# ADC.net
KiCad netlist of a schematic drawn in Altium Designer
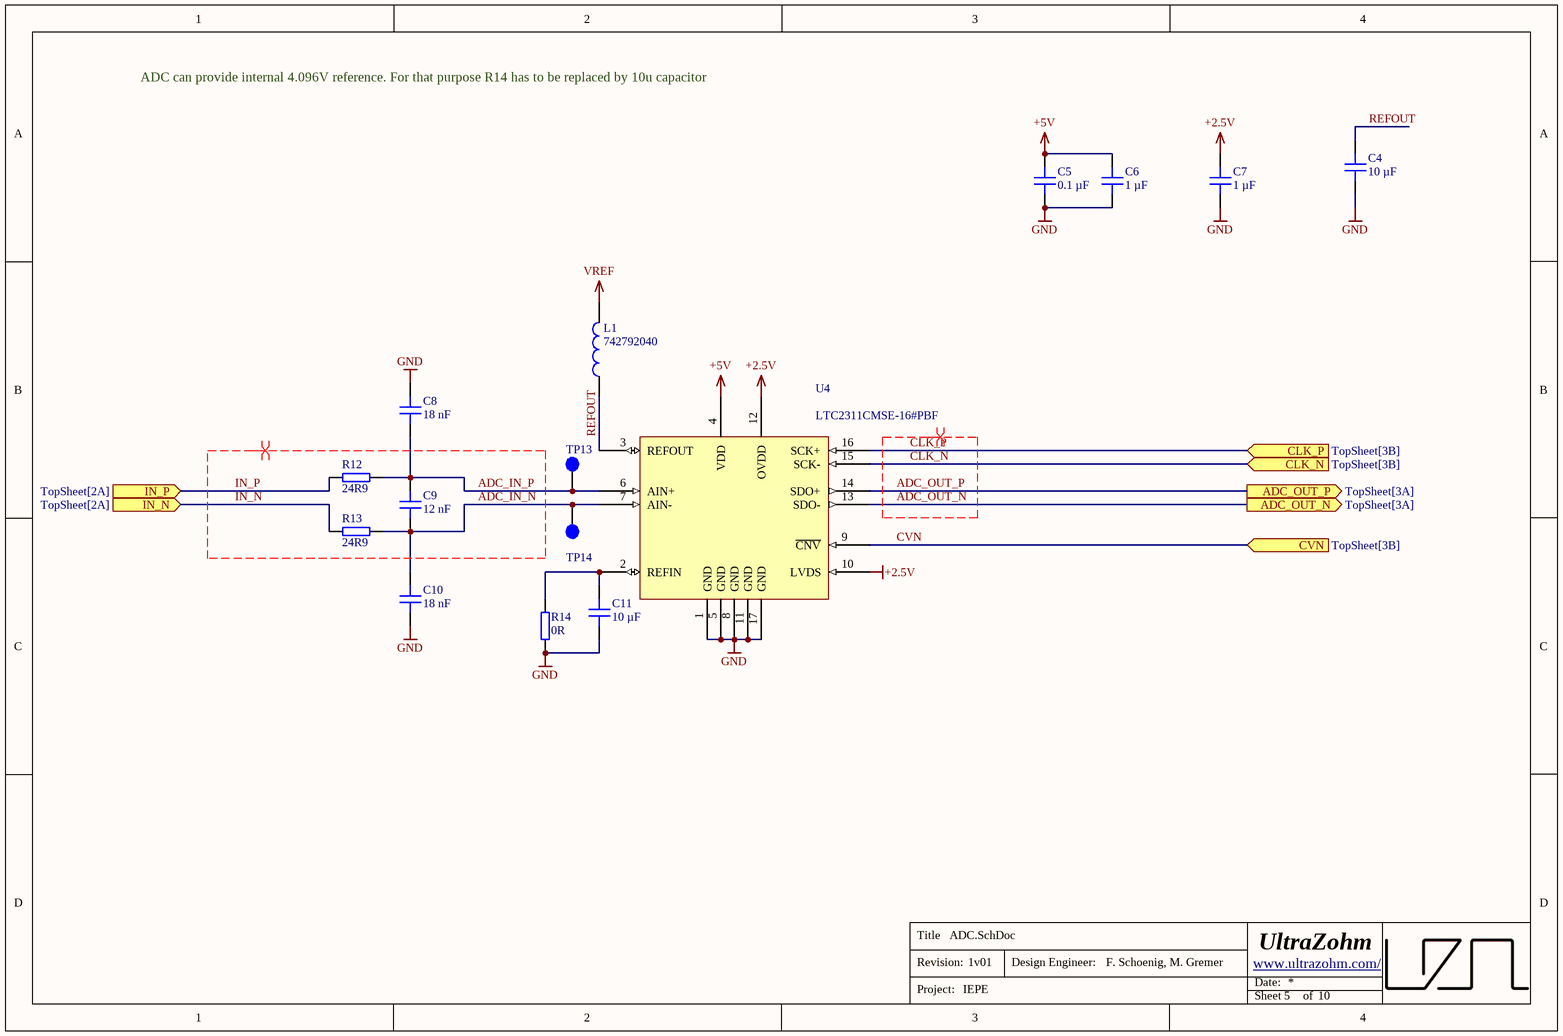
[diagram p0: ADC.SchDoc]

(export (version "E")
  (design (tool "Eeschema 10.0.6"))
  (components
    (comp (ref "C4")
      (value "10 µF")
      (footprint "C_0805")
      (description "Capacitor 0805, 25 VDC, 10 µF, X5R")
      (fields
        (field (name "MANUFACTURER PART NUMBER") "GRM219R61E106KA12D")
        (field (name "MANUFACTURER") "muRata")
        (field (name "CREATED FROM") "MGremer")
      )
      (libsource (lib "user") (part "Capacitor"))
    )
    (comp (ref "C5")
      (value "0.1 µF")
      (footprint "C_0603")
      (description "Capacitor 0603, 50 VDC, 0.1 µF, X7R")
      (fields
        (field (name "MANUFACTURER PART NUMBER") "C0603X104K5RAC7411")
        (field (name "MANUFACTURER") "KEMET")
        (field (name "CREATED FROM") "MGremer")
      )
      (libsource (lib "user") (part "Capacitor"))
    )
    (comp (ref "C6")
      (value "1 µF")
      (footprint "C_0603")
      (description "Capacitor 0603, 6.3 VDC, 1 µF, X7R")
      (fields
        (field (name "MANUFACTURER PART NUMBER") "JMK107BJ105MA-T")
        (field (name "MANUFACTURER") "Tajyo Yuden")
        (field (name "CREATED FROM") "MGremer")
      )
      (libsource (lib "user") (part "Capacitor"))
    )
    (comp (ref "C7")
      (value "1 µF")
      (footprint "C_0603")
      (description "Capacitor 0603, 6.3 VDC, 1 µF, X7R")
      (fields
        (field (name "MANUFACTURER PART NUMBER") "JMK107BJ105MA-T")
        (field (name "MANUFACTURER") "Tajyo Yuden")
        (field (name "CREATED FROM") "MGremer")
      )
      (libsource (lib "user") (part "Capacitor"))
    )
    (comp (ref "C8")
      (value "18 nF")
      (footprint "C_0603")
      (description "Capacitor 0603, 16 VDC, 18 nF, X7R")
      (fields
        (field (name "MANUFACTURER PART NUMBER") "C0603C183K4RACTU")
        (field (name "MANUFACTURER") "KEMET")
        (field (name "CREATED FROM") "MGremer")
      )
      (libsource (lib "user") (part "Capacitor"))
    )
    (comp (ref "C9")
      (value "12 nF")
      (footprint "C_0603")
      (description "Capacitor 0603, 16 VDC, 12 nF, X7R")
      (fields
        (field (name "MANUFACTURER PART NUMBER") "CC0603KRX7R7BB123")
        (field (name "MANUFACTURER") "Yageo")
        (field (name "CREATED FROM") "MGremer")
      )
      (libsource (lib "user") (part "Capacitor"))
    )
    (comp (ref "C10")
      (value "18 nF")
      (footprint "C_0603")
      (description "Capacitor 0603, 16 VDC, 18 nF, X7R")
      (fields
        (field (name "MANUFACTURER PART NUMBER") "C0603C183K4RACTU")
        (field (name "MANUFACTURER") "KEMET")
        (field (name "CREATED FROM") "MGremer")
      )
      (libsource (lib "user") (part "Capacitor"))
    )
    (comp (ref "C11")
      (value "10 µF")
      (footprint "C_0805")
      (description "Capacitor 0805, 25 VDC, 10 µF, X5R")
      (fields
        (field (name "MANUFACTURER PART NUMBER") "GRM219R61E106KA12D")
        (field (name "MANUFACTURER") "muRata")
        (field (name "CREATED FROM") "MGremer")
      )
      (libsource (lib "user") (part "Capacitor"))
    )
    (comp (ref "L1")
      (value "742792040")
      (footprint "WE-CBF_0805_High Current")
      (description "Inductance, 0805, 100 MHz, 600 Ohm, 2 A")
      (fields (field (name "MANUFACTURER") "Wurth Elektronik") (field (name "CREATED FROM") "MGremer"))
      (libsource (lib "user") (part "WE-CBF"))
    )
    (comp (ref "R12")
      (value "24R9")
      (footprint "RES 0603_1608")
      (description "SMD resistor 1%")
      (fields
        (field (name "MANUFACTURER PART NUMBER") "RC0603FR-1324R9L")
        (field (name "MANUFACTURER") "Yageo")
        (field (name "CREATED FROM") "MGremer")
      )
      (libsource (lib "user") (part "Resistor"))
    )
    (comp (ref "R13")
      (value "24R9")
      (footprint "RES 0603_1608")
      (description "SMD resistor 1%")
      (fields
        (field (name "MANUFACTURER PART NUMBER") "RC0603FR-1324R9L")
        (field (name "MANUFACTURER") "Yageo")
        (field (name "CREATED FROM") "MGremer")
      )
      (libsource (lib "user") (part "Resistor"))
    )
    (comp (ref "R14")
      (value "0R")
      (footprint "RES 0603_1608")
      (description "SMD resistor E24 series")
      (fields
        (field (name "MANUFACTURER PART NUMBER") "RC0603JR-070RL")
        (field (name "MANUFACTURER") "YAGEO")
        (field (name "CREATED FROM") "MGremer")
      )
      (libsource (lib "user") (part "Resistor"))
    )
    (comp (ref "TP13")
      (value "-")
      (footprint "TP_1mm")
      (description "Test Point 1 mm")
      (fields (field (name "CREATED") "2018_06_25_AGeiger") (field (name "CREATED FROM") "MGremer"))
      (libsource (lib "user") (part "TP_1mm"))
    )
    (comp (ref "TP14")
      (value "-")
      (footprint "TP_1mm")
      (description "Test Point 1 mm")
      (fields (field (name "CREATED") "2018_06_25_AGeiger") (field (name "CREATED FROM") "MGremer"))
      (libsource (lib "user") (part "TP_1mm"))
    )
    (comp (ref "U4")
      (value "LTC2311CMSE-16#PBF")
      (footprint "TSSOP50P510X110_HS-17N")
      (description "Differential Input ADC with Wide Input Common Mode Range")
      (fields (field (name "MANUFACTURER") "Analog Devices") (field (name "CREATED FROM") "MGremer"))
      (libsource (lib "user") (part "LTC2311-16"))
    )
  )
  (nets
    (net (code "1") (name "+2.5V") (class "Default")
      (node (ref "C7") (pin "2") (pinfunction "2_2") (pintype "passive"))
      (node (ref "U4") (pin "10") (pinfunction "LVDS_10") (pintype "input"))
      (node (ref "U4") (pin "12") (pinfunction "OVDD_12") (pintype "power_in"))
    )
    (net (code "2") (name "+5V") (class "Default")
      (node (ref "C5") (pin "2") (pinfunction "2_2") (pintype "passive"))
      (node (ref "C6") (pin "2") (pinfunction "2_2") (pintype "passive"))
      (node (ref "U4") (pin "4") (pinfunction "VDD_4") (pintype "power_in"))
    )
    (net (code "3") (name "/ADC_IN_N") (class "Default")
      (node (ref "C10") (pin "2") (pinfunction "2_2") (pintype "passive"))
      (node (ref "C9") (pin "1") (pinfunction "1_1") (pintype "passive"))
      (node (ref "R13") (pin "2") (pinfunction "2_2") (pintype "passive"))
      (node (ref "TP14") (pin "1") (pintype "passive"))
      (node (ref "U4") (pin "7") (pinfunction "AIN-_7") (pintype "input"))
    )
    (net (code "4") (name "/ADC_IN_P") (class "Default")
      (node (ref "C8") (pin "1") (pinfunction "1_1") (pintype "passive"))
      (node (ref "C9") (pin "2") (pinfunction "2_2") (pintype "passive"))
      (node (ref "R12") (pin "2") (pinfunction "2_2") (pintype "passive"))
      (node (ref "TP13") (pin "1") (pintype "passive"))
      (node (ref "U4") (pin "6") (pinfunction "AIN+_6") (pintype "input"))
    )
    (net (code "5") (name "/ADC_OUT_N") (class "Default")
      (node (ref "U4") (pin "13") (pinfunction "SDO-_13") (pintype "output"))
    )
    (net (code "6") (name "/ADC_OUT_P") (class "Default")
      (node (ref "U4") (pin "14") (pinfunction "SDO+_14") (pintype "output"))
    )
    (net (code "7") (name "/CLK_N") (class "Default")
      (node (ref "U4") (pin "15") (pinfunction "SCK-_15") (pintype "input"))
    )
    (net (code "8") (name "/CLK_P") (class "Default")
      (node (ref "U4") (pin "16") (pinfunction "SCK+_16") (pintype "input"))
    )
    (net (code "9") (name "/CVN") (class "Default")
      (node (ref "U4") (pin "9") (pinfunction "~{CNV}_9") (pintype "input"))
    )
    (net (code "10") (name "/IN_N") (class "Default")
      (node (ref "R13") (pin "1") (pinfunction "1_1") (pintype "passive"))
    )
    (net (code "11") (name "/IN_P") (class "Default")
      (node (ref "R12") (pin "1") (pinfunction "1_1") (pintype "passive"))
    )
    (net (code "12") (name "/REFOUT") (class "Default")
      (node (ref "C4") (pin "2") (pinfunction "2_2") (pintype "passive"))
      (node (ref "L1") (pin "1") (pinfunction "1_1") (pintype "passive"))
      (node (ref "U4") (pin "3") (pinfunction "REFOUT_3") (pintype "bidirectional"))
    )
    (net (code "13") (name "GND") (class "Default")
      (node (ref "C10") (pin "1") (pinfunction "1_1") (pintype "passive"))
      (node (ref "C11") (pin "1") (pinfunction "1_1") (pintype "passive"))
      (node (ref "C4") (pin "1") (pinfunction "1_1") (pintype "passive"))
      (node (ref "C5") (pin "1") (pinfunction "1_1") (pintype "passive"))
      (node (ref "C6") (pin "1") (pinfunction "1_1") (pintype "passive"))
      (node (ref "C7") (pin "1") (pinfunction "1_1") (pintype "passive"))
      (node (ref "C8") (pin "2") (pinfunction "2_2") (pintype "passive"))
      (node (ref "R14") (pin "1") (pinfunction "1_1") (pintype "passive"))
      (node (ref "U4") (pin "1") (pinfunction "GND_1") (pintype "power_in"))
      (node (ref "U4") (pin "11") (pinfunction "GND_11") (pintype "power_in"))
      (node (ref "U4") (pin "17") (pinfunction "GND_17") (pintype "power_in"))
      (node (ref "U4") (pin "5") (pinfunction "GND_5") (pintype "power_in"))
      (node (ref "U4") (pin "8") (pinfunction "GND_8") (pintype "power_in"))
    )
    (net (code "14") (name "Net-(U4-REFIN)") (class "Default")
      (node (ref "C11") (pin "2") (pinfunction "2_2") (pintype "passive"))
      (node (ref "R14") (pin "2") (pinfunction "2_2") (pintype "passive"))
      (node (ref "U4") (pin "2") (pinfunction "REFIN_2") (pintype "bidirectional"))
    )
    (net (code "15") (name "VREF") (class "Default")
      (node (ref "L1") (pin "2") (pinfunction "2_2") (pintype "passive"))
    )
  )
)
